# RGB_Station_v11.net
KiCad netlist of a schematic drawn in EAGLE
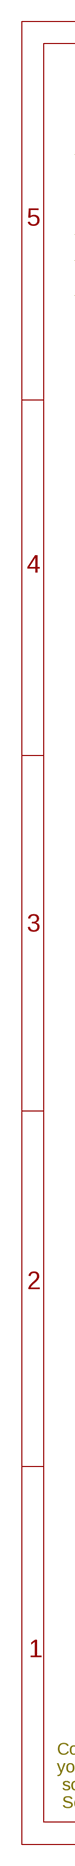
[diagram p0: schematic, sheet 1, part 1 of 2]
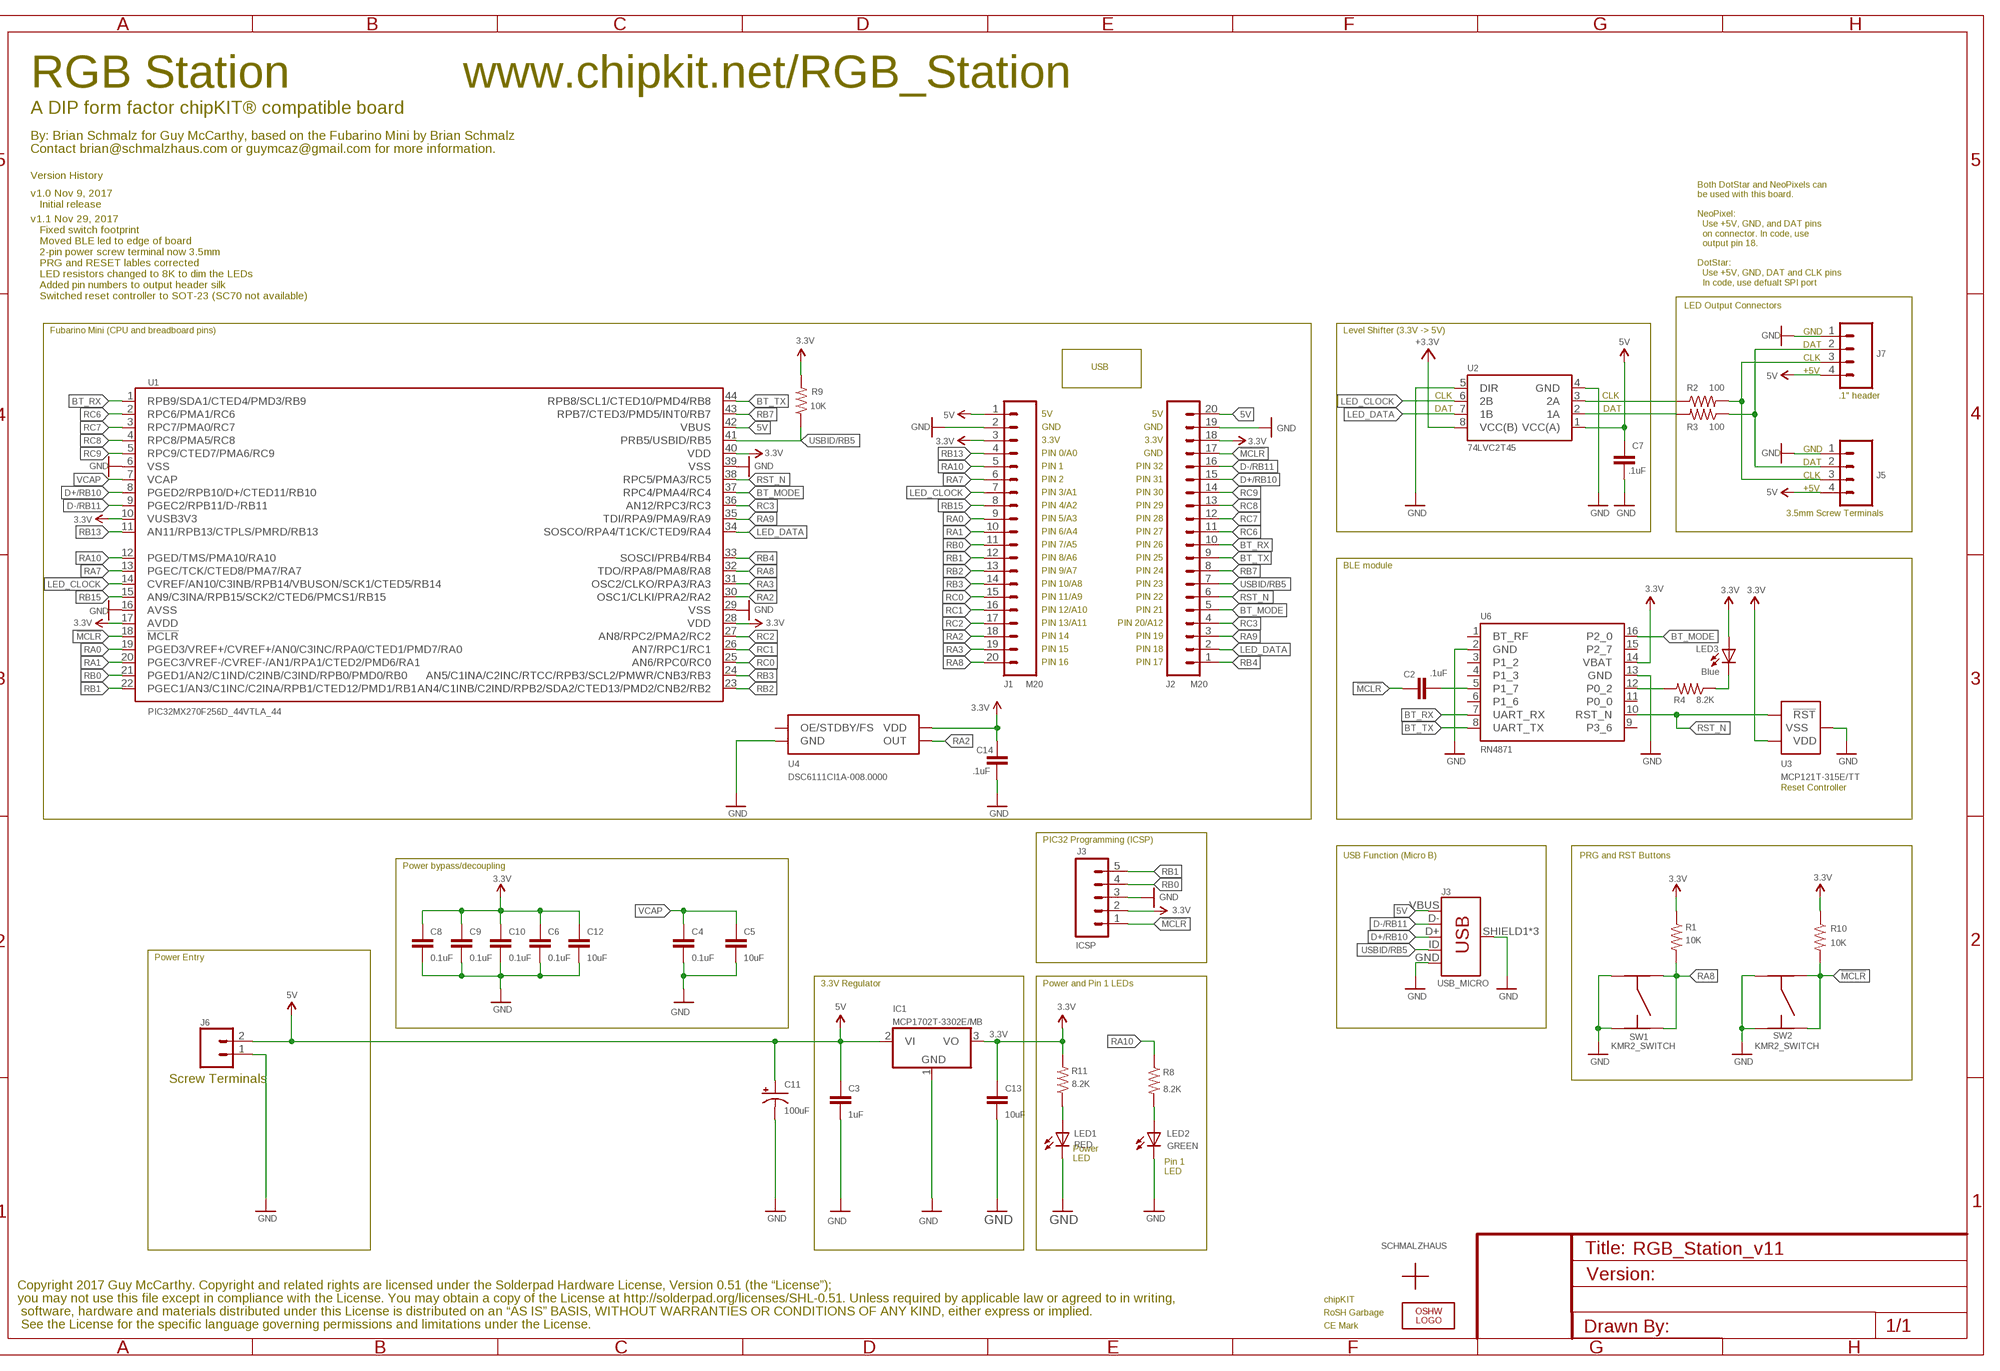
[diagram p1: schematic, sheet 1, part 2 of 2]

(export (version "E")
  (design (tool "Eeschema 10.0.6"))
  (components
    (comp (ref "C2")
      (value ".1uF")
      (footprint "eagle-import:0603-CAP")
      (libsource (lib "eagle-import") (part "SparkFun-Capacitors_CAP0603-CAP"))
    )
    (comp (ref "C3")
      (value "1uF")
      (footprint "eagle-import:0603-CAP")
      (libsource (lib "eagle-import") (part "SparkFun_CAP0603-CAP"))
    )
    (comp (ref "C4")
      (value "0.1uF")
      (footprint "eagle-import:0603-CAP")
      (libsource (lib "eagle-import") (part "SparkFun_CAP0603-CAP"))
    )
    (comp (ref "C5")
      (value "10uF")
      (footprint "eagle-import:0805")
      (libsource (lib "eagle-import") (part "CAP0805"))
    )
    (comp (ref "C6")
      (value "0.1uF")
      (footprint "eagle-import:0603")
      (libsource (lib "eagle-import") (part "CAP0603"))
    )
    (comp (ref "C7")
      (value ".1uF")
      (footprint "eagle-import:0603-CAP")
      (libsource (lib "eagle-import") (part "SparkFun-Capacitors_CAP0603-CAP"))
    )
    (comp (ref "C8")
      (value "0.1uF")
      (footprint "eagle-import:0603-CAP")
      (libsource (lib "eagle-import") (part "SparkFun_CAP0603-CAP"))
    )
    (comp (ref "C9")
      (value "0.1uF")
      (footprint "eagle-import:0603-CAP")
      (libsource (lib "eagle-import") (part "SparkFun_CAP0603-CAP"))
    )
    (comp (ref "C10")
      (value "0.1uF")
      (footprint "eagle-import:0603")
      (libsource (lib "eagle-import") (part "CAP0603"))
    )
    (comp (ref "C11")
      (value "100uF")
      (footprint "eagle-import:PANASONIC_C")
      (libsource (lib "eagle-import") (part "CAP_POLC"))
    )
    (comp (ref "C12")
      (value "10uF")
      (footprint "eagle-import:0805")
      (libsource (lib "eagle-import") (part "CAP0805"))
    )
    (comp (ref "C13")
      (value "10uF")
      (footprint "eagle-import:0805")
      (libsource (lib "eagle-import") (part "SparkFun02-20-08_CAP0805"))
    )
    (comp (ref "C14")
      (value ".1uF")
      (footprint "eagle-import:0603-CAP")
      (libsource (lib "eagle-import") (part "SparkFun_CAP0603-CAP"))
    )
    (comp (ref "IC1")
      (value "MCP1702T-3302E/MB")
      (footprint "eagle-import:SOT89")
      (libsource (lib "eagle-import") (part "MCP1703MB33"))
    )
    (comp (ref "ICSP")
      (value "J3")
      (footprint "eagle-import:1X05_NOSILK")
      (libsource (lib "eagle-import") (part "M05NOSLILK"))
    )
    (comp (ref "J1")
      (value "M20")
      (footprint "eagle-import:1X20_NO_PIN1")
      (libsource (lib "eagle-import") (part "M20"))
    )
    (comp (ref "J2")
      (value "M20")
      (footprint "eagle-import:1X20_NO_PIN1")
      (libsource (lib "eagle-import") (part "M20"))
    )
    (comp (ref "J3")
      (value "USB_MICRO")
      (footprint "eagle-import:USB-B-MICRO-SMD")
      (libsource (lib "eagle-import") (part "USB_MICRO-B_FEMALE-SMT"))
    )
    (comp (ref "J5")
      (value "CONN_04SCREW")
      (footprint "eagle-import:SCREWTERMINAL-3.5MM-4@1")
      (libsource (lib "eagle-import") (part "CONN_04SCREW"))
    )
    (comp (ref "J6")
      (value "CONN_023.5MM")
      (footprint "eagle-import:SCREWTERMINAL-3.5MM-2")
      (libsource (lib "eagle-import") (part "CONN_023.5MM"))
    )
    (comp (ref "J7")
      (value "M04PTH")
      (footprint "eagle-import:1X04")
      (libsource (lib "eagle-import") (part "M04PTH"))
    )
    (comp (ref "LED1")
      (value "RED")
      (footprint "eagle-import:LED-0603")
      (libsource (lib "eagle-import") (part "LED0603"))
    )
    (comp (ref "LED2")
      (value "GREEN")
      (footprint "eagle-import:LED-0603")
      (libsource (lib "eagle-import") (part "LED0603"))
    )
    (comp (ref "LED3")
      (value "Blue")
      (footprint "eagle-import:LED-0603")
      (libsource (lib "eagle-import") (part "LED0603"))
    )
    (comp (ref "LOGO1")
      (value "OSHW_LOGO_8MILX0070-NT")
      (footprint "eagle-import:OSHW_8X70_NOTEXT")
      (libsource (lib "eagle-import") (part "OSHW_LOGO_8MILX0070-NT"))
    )
    (comp (ref "R1")
      (value "10K")
      (footprint "eagle-import:0603-RES")
      (libsource (lib "eagle-import") (part "RESISTOR0603-RES"))
    )
    (comp (ref "R2")
      (value "100")
      (footprint "eagle-import:0603-RES")
      (libsource (lib "eagle-import") (part "RESISTOR0603"))
    )
    (comp (ref "R3")
      (value "100")
      (footprint "eagle-import:0603-RES")
      (libsource (lib "eagle-import") (part "RESISTOR0603"))
    )
    (comp (ref "R4")
      (value "8.2K")
      (footprint "eagle-import:0603-RES")
      (libsource (lib "eagle-import") (part "RESISTOR0603-RES"))
    )
    (comp (ref "R8")
      (value "8.2K")
      (footprint "eagle-import:0603-RES")
      (libsource (lib "eagle-import") (part "RESISTOR0603-RES"))
    )
    (comp (ref "R9")
      (value "10K")
      (footprint "eagle-import:0603-RES")
      (libsource (lib "eagle-import") (part "RESISTOR0603-RES"))
    )
    (comp (ref "R10")
      (value "10K")
      (footprint "eagle-import:0603-RES")
      (libsource (lib "eagle-import") (part "RESISTOR0603-RES"))
    )
    (comp (ref "R11")
      (value "8.2K")
      (footprint "eagle-import:0603-RES")
      (libsource (lib "eagle-import") (part "RESISTOR0603-RES"))
    )
    (comp (ref "SW1")
      (value "KMR2_SWITCH")
      (footprint "eagle-import:KMR2_SWITCH")
      (libsource (lib "eagle-import") (part "KMR2_SWITCH"))
    )
    (comp (ref "SW2")
      (value "KMR2_SWITCH")
      (footprint "eagle-import:KMR2_SWITCH")
      (libsource (lib "eagle-import") (part "KMR2_SWITCH"))
    )
    (comp (ref "U$2")
      (value "CE_MARK5MM")
      (footprint "eagle-import:CE_5MM")
      (libsource (lib "eagle-import") (part "CE_MARK5MM"))
    )
    (comp (ref "U$3")
      (value "ROSH_GARBAGE")
      (footprint "eagle-import:ROHS_GARBAGE_5MM")
      (libsource (lib "eagle-import") (part "ROSH_GARBAGE"))
    )
    (comp (ref "U$4")
      (value "CHIPKIT2MM")
      (footprint "eagle-import:CHIPKIT_2MM")
      (libsource (lib "eagle-import") (part "CHIPKIT2MM"))
    )
    (comp (ref "U$5")
      (value "SCHMALZHAUSSCHMALZHAUS_SMALL")
      (footprint "eagle-import:SCHMALZHAUS_SMALL")
      (libsource (lib "eagle-import") (part "SCHMALZHAUSSCHMALZHAUS_SMALL"))
    )
    (comp (ref "U1")
      (value "PIC32MX270F256D_44VTLA_44")
      (footprint "eagle-import:QFN-44-8X8-NOPAD")
      (libsource (lib "eagle-import") (part "PIC32MX2XX_44QFN44"))
    )
    (comp (ref "U2")
      (value "74LVC2T45")
      (footprint "eagle-import:VSSOP8")
      (libsource (lib "eagle-import") (part "74LVC2T45"))
    )
    (comp (ref "U3")
      (value "MCP121T-315E/TT")
      (footprint "eagle-import:SOT23-3")
      (libsource (lib "eagle-import") (part "MCP1X2_RESET_CONTROLLER"))
    )
    (comp (ref "U4")
      (value "DSC6111CI1A-008.0000")
      (footprint "eagle-import:CDFN-4_3.2X2.5")
      (libsource (lib "eagle-import") (part "DSC61XX"))
    )
    (comp (ref "U6")
      (value "RN4871")
      (footprint "eagle-import:RN4871")
      (libsource (lib "eagle-import") (part "RN4871"))
    )
  )
  (nets
    (net (code "1") (name "+3.3V") (class "Default")
      (node (ref "C10") (pin "1") (pinfunction "1_1") (pintype "passive"))
      (node (ref "C12") (pin "1") (pinfunction "1_1") (pintype "passive"))
      (node (ref "C13") (pin "1") (pinfunction "1_1") (pintype "passive"))
      (node (ref "C14") (pin "2") (pinfunction "2_2") (pintype "passive"))
      (node (ref "C6") (pin "1") (pinfunction "1_1") (pintype "passive"))
      (node (ref "C8") (pin "1") (pinfunction "1_1") (pintype "passive"))
      (node (ref "C9") (pin "1") (pinfunction "1_1") (pintype "passive"))
      (node (ref "IC1") (pin "3") (pinfunction "VO_3") (pintype "passive"))
      (node (ref "ICSP") (pin "2") (pinfunction "2_2") (pintype "passive"))
      (node (ref "J1") (pin "3") (pinfunction "3_3") (pintype "passive"))
      (node (ref "J2") (pin "18") (pinfunction "18_18") (pintype "passive"))
      (node (ref "LED3") (pin "A") (pinfunction "A_A") (pintype "passive"))
      (node (ref "R1") (pin "1") (pinfunction "1_1") (pintype "passive"))
      (node (ref "R10") (pin "1") (pinfunction "1_1") (pintype "passive"))
      (node (ref "R11") (pin "2") (pinfunction "2_2") (pintype "passive"))
      (node (ref "R9") (pin "2") (pinfunction "2_2") (pintype "passive"))
      (node (ref "U1") (pin "10") (pinfunction "VUSB3V3_10") (pintype "bidirectional"))
      (node (ref "U1") (pin "17") (pinfunction "AVDD_17") (pintype "bidirectional"))
      (node (ref "U1") (pin "28") (pinfunction "VDD_28") (pintype "bidirectional"))
      (node (ref "U1") (pin "40") (pinfunction "VDD_40") (pintype "bidirectional"))
      (node (ref "U2") (pin "8") (pinfunction "VCC(B)_8") (pintype "bidirectional"))
      (node (ref "U3") (pin "2") (pinfunction "VDD_2") (pintype "bidirectional"))
      (node (ref "U4") (pin "P4") (pinfunction "VDD_P4") (pintype "bidirectional"))
      (node (ref "U6") (pin "14") (pinfunction "VBAT_14") (pintype "bidirectional"))
    )
    (net (code "2") (name "/~{MCLR}") (class "Default")
      (node (ref "C2") (pin "2") (pinfunction "2_2") (pintype "passive"))
      (node (ref "ICSP") (pin "1") (pinfunction "1_1") (pintype "passive"))
      (node (ref "J2") (pin "17") (pinfunction "17_17") (pintype "passive"))
      (node (ref "R10") (pin "2") (pinfunction "2_2") (pintype "passive"))
      (node (ref "SW2") (pin "P3") (pinfunction "P3_P3") (pintype "bidirectional"))
      (node (ref "SW2") (pin "P4") (pinfunction "P4_P4") (pintype "bidirectional"))
      (node (ref "U1") (pin "18") (pinfunction "~{MCLR}_18") (pintype "bidirectional"))
    )
    (net (code "3") (name "5V") (class "Default")
      (node (ref "C11") (pin "+") (pinfunction "+_+") (pintype "passive"))
      (node (ref "C3") (pin "1") (pinfunction "1_1") (pintype "passive"))
      (node (ref "C7") (pin "2") (pinfunction "2_2") (pintype "passive"))
      (node (ref "IC1") (pin "2") (pinfunction "VI_2") (pintype "input"))
      (node (ref "IC1") (pin "2@1") (pinfunction "VI1_2@1") (pintype "input"))
      (node (ref "J1") (pin "1") (pinfunction "1_1") (pintype "passive"))
      (node (ref "J2") (pin "20") (pinfunction "20_20") (pintype "passive"))
      (node (ref "J3") (pin "VBUS") (pinfunction "VBUS_VBUS") (pintype "power_in"))
      (node (ref "J5") (pin "4") (pinfunction "4_4") (pintype "passive"))
      (node (ref "J6") (pin "2") (pinfunction "2_2") (pintype "passive"))
      (node (ref "J7") (pin "4") (pinfunction "4_4") (pintype "passive"))
      (node (ref "U1") (pin "42") (pinfunction "VBUS_42") (pintype "bidirectional"))
      (node (ref "U2") (pin "1") (pinfunction "VCC(A)_1") (pintype "bidirectional"))
    )
    (net (code "4") (name "BT_MODE") (class "Default")
      (node (ref "J2") (pin "5") (pinfunction "5_5") (pintype "passive"))
      (node (ref "U1") (pin "37") (pinfunction "RPC4/PMA4/RC4_37") (pintype "bidirectional"))
      (node (ref "U6") (pin "16") (pinfunction "P2_0_16") (pintype "bidirectional"))
    )
    (net (code "5") (name "BT_RX") (class "Default")
      (node (ref "J2") (pin "10") (pinfunction "10_10") (pintype "passive"))
      (node (ref "U1") (pin "1") (pinfunction "RPB9/SDA1/CTED4/PMD3/RB9_1") (pintype "bidirectional"))
      (node (ref "U6") (pin "7") (pinfunction "UART_RX_7") (pintype "bidirectional"))
    )
    (net (code "6") (name "BT_TX") (class "Default")
      (node (ref "J2") (pin "9") (pinfunction "9_9") (pintype "passive"))
      (node (ref "U1") (pin "44") (pinfunction "RPB8/SCL1/CTED10/PMD4/RB8_44") (pintype "bidirectional"))
      (node (ref "U6") (pin "8") (pinfunction "UART_TX_8") (pintype "bidirectional"))
    )
    (net (code "7") (name "D+{slash}RB10") (class "Default")
      (node (ref "J2") (pin "15") (pinfunction "15_15") (pintype "passive"))
      (node (ref "J3") (pin "D+") (pinfunction "D+_D+") (pintype "bidirectional"))
      (node (ref "U1") (pin "8") (pinfunction "PGED2/RPB10/D+/CTED11/RB10_8") (pintype "bidirectional"))
    )
    (net (code "8") (name "D-{slash}RB11") (class "Default")
      (node (ref "J2") (pin "16") (pinfunction "16_16") (pintype "passive"))
      (node (ref "J3") (pin "D-") (pinfunction "D-_D-") (pintype "bidirectional"))
      (node (ref "U1") (pin "9") (pinfunction "PGEC2/RPB11/D-/RB11_9") (pintype "bidirectional"))
    )
    (net (code "9") (name "GND") (class "Default")
      (node (ref "C10") (pin "2") (pinfunction "2_2") (pintype "passive"))
      (node (ref "C11") (pin "-") (pinfunction "-_-") (pintype "passive"))
      (node (ref "C12") (pin "2") (pinfunction "2_2") (pintype "passive"))
      (node (ref "C13") (pin "2") (pinfunction "2_2") (pintype "passive"))
      (node (ref "C14") (pin "1") (pinfunction "1_1") (pintype "passive"))
      (node (ref "C3") (pin "2") (pinfunction "2_2") (pintype "passive"))
      (node (ref "C4") (pin "2") (pinfunction "2_2") (pintype "passive"))
      (node (ref "C5") (pin "2") (pinfunction "2_2") (pintype "passive"))
      (node (ref "C6") (pin "2") (pinfunction "2_2") (pintype "passive"))
      (node (ref "C7") (pin "1") (pinfunction "1_1") (pintype "passive"))
      (node (ref "C8") (pin "2") (pinfunction "2_2") (pintype "passive"))
      (node (ref "C9") (pin "2") (pinfunction "2_2") (pintype "passive"))
      (node (ref "IC1") (pin "1") (pinfunction "GND_1") (pintype "passive"))
      (node (ref "ICSP") (pin "3") (pinfunction "3_3") (pintype "passive"))
      (node (ref "J1") (pin "2") (pinfunction "2_2") (pintype "passive"))
      (node (ref "J2") (pin "19") (pinfunction "19_19") (pintype "passive"))
      (node (ref "J3") (pin "GND") (pinfunction "GND_GND") (pintype "power_in"))
      (node (ref "J3") (pin "SHIELD1") (pinfunction "SHIELD_SHIELD1") (pintype "bidirectional"))
      (node (ref "J3") (pin "SHIELD2") (pinfunction "SHIELD_SHIELD2") (pintype "bidirectional"))
      (node (ref "J3") (pin "SHIELD3") (pinfunction "SHIELD_SHIELD3") (pintype "bidirectional"))
      (node (ref "J5") (pin "1") (pinfunction "1_1") (pintype "passive"))
      (node (ref "J6") (pin "1") (pinfunction "1_1") (pintype "passive"))
      (node (ref "J7") (pin "1") (pinfunction "1_1") (pintype "passive"))
      (node (ref "LED1") (pin "C") (pinfunction "C_C") (pintype "passive"))
      (node (ref "LED2") (pin "C") (pinfunction "C_C") (pintype "passive"))
      (node (ref "SW1") (pin "P1") (pinfunction "P1_P1") (pintype "bidirectional"))
      (node (ref "SW1") (pin "P2") (pinfunction "P2_P2") (pintype "bidirectional"))
      (node (ref "SW2") (pin "P1") (pinfunction "P1_P1") (pintype "bidirectional"))
      (node (ref "SW2") (pin "P2") (pinfunction "P2_P2") (pintype "bidirectional"))
      (node (ref "U1") (pin "16") (pinfunction "AVSS_16") (pintype "bidirectional"))
      (node (ref "U1") (pin "29") (pinfunction "VSS_29") (pintype "bidirectional"))
      (node (ref "U1") (pin "39") (pinfunction "VSS_39") (pintype "bidirectional"))
      (node (ref "U1") (pin "6") (pinfunction "VSS_6") (pintype "bidirectional"))
      (node (ref "U2") (pin "4") (pinfunction "GND_4") (pintype "bidirectional"))
      (node (ref "U2") (pin "5") (pinfunction "DIR_5") (pintype "bidirectional"))
      (node (ref "U3") (pin "3") (pinfunction "VSS_3") (pintype "bidirectional"))
      (node (ref "U4") (pin "P2") (pinfunction "GND_P2") (pintype "bidirectional"))
      (node (ref "U6") (pin "13") (pinfunction "GND_13") (pintype "bidirectional"))
      (node (ref "U6") (pin "2") (pinfunction "GND_2") (pintype "bidirectional"))
    )
    (net (code "10") (name "LED_CLOCK") (class "Default")
      (node (ref "J1") (pin "7") (pinfunction "7_7") (pintype "passive"))
      (node (ref "U1") (pin "14") (pinfunction "CVREF/AN10/C3INB/RPB14/VBUSON/SCK1/CTED5/RB14_14") (pintype "bidirectional"))
      (node (ref "U2") (pin "6") (pinfunction "2B_6") (pintype "bidirectional"))
    )
    (net (code "11") (name "LED_DATA") (class "Default")
      (node (ref "J2") (pin "2") (pinfunction "2_2") (pintype "passive"))
      (node (ref "U1") (pin "34") (pinfunction "SOSCO/RPA4/T1CK/CTED9/RA4_34") (pintype "bidirectional"))
      (node (ref "U2") (pin "7") (pinfunction "1B_7") (pintype "bidirectional"))
    )
    (net (code "12") (name "Net-(J5-Pad2)") (class "Default")
      (node (ref "J5") (pin "2") (pinfunction "2_2") (pintype "passive"))
      (node (ref "J7") (pin "2") (pinfunction "2_2") (pintype "passive"))
      (node (ref "R3") (pin "1") (pinfunction "1_1") (pintype "passive"))
    )
    (net (code "13") (name "Net-(J5-Pad3)") (class "Default")
      (node (ref "J5") (pin "3") (pinfunction "3_3") (pintype "passive"))
      (node (ref "J7") (pin "3") (pinfunction "3_3") (pintype "passive"))
      (node (ref "R2") (pin "2") (pinfunction "2_2") (pintype "passive"))
    )
    (net (code "14") (name "Net-(LED1-PadA)") (class "Default")
      (node (ref "LED1") (pin "A") (pinfunction "A_A") (pintype "passive"))
      (node (ref "R11") (pin "1") (pinfunction "1_1") (pintype "passive"))
    )
    (net (code "15") (name "Net-(LED2-PadA)") (class "Default")
      (node (ref "LED2") (pin "A") (pinfunction "A_A") (pintype "passive"))
      (node (ref "R8") (pin "2") (pinfunction "2_2") (pintype "passive"))
    )
    (net (code "16") (name "Net-(LED3-PadC)") (class "Default")
      (node (ref "LED3") (pin "C") (pinfunction "C_C") (pintype "passive"))
      (node (ref "R4") (pin "1") (pinfunction "1_1") (pintype "passive"))
    )
    (net (code "17") (name "Net-(U2-1A)") (class "Default")
      (node (ref "R3") (pin "2") (pinfunction "2_2") (pintype "passive"))
      (node (ref "U2") (pin "2") (pinfunction "1A_2") (pintype "bidirectional"))
    )
    (net (code "18") (name "Net-(U2-2A)") (class "Default")
      (node (ref "R2") (pin "1") (pinfunction "1_1") (pintype "passive"))
      (node (ref "U2") (pin "3") (pinfunction "2A_3") (pintype "bidirectional"))
    )
    (net (code "19") (name "Net-(U6-P0_2)") (class "Default")
      (node (ref "R4") (pin "2") (pinfunction "2_2") (pintype "passive"))
      (node (ref "U6") (pin "12") (pinfunction "P0_2_12") (pintype "bidirectional"))
    )
    (net (code "20") (name "Net-(U6-P1_7)") (class "Default")
      (node (ref "C2") (pin "1") (pinfunction "1_1") (pintype "passive"))
      (node (ref "U6") (pin "5") (pinfunction "P1_7_5") (pintype "bidirectional"))
    )
    (net (code "21") (name "RA0") (class "Default")
      (node (ref "J1") (pin "9") (pinfunction "9_9") (pintype "passive"))
      (node (ref "U1") (pin "19") (pinfunction "PGED3/VREF+/CVREF+/AN0/C3INC/RPA0/CTED1/PMD7/RA0_19") (pintype "bidirectional"))
    )
    (net (code "22") (name "RA1") (class "Default")
      (node (ref "J1") (pin "10") (pinfunction "10_10") (pintype "passive"))
      (node (ref "U1") (pin "20") (pinfunction "PGEC3/VREF-/CVREF-/AN1/RPA1/CTED2/PMD6/RA1_20") (pintype "bidirectional"))
    )
    (net (code "23") (name "RA2") (class "Default")
      (node (ref "J1") (pin "18") (pinfunction "18_18") (pintype "passive"))
      (node (ref "U1") (pin "30") (pinfunction "OSC1/CLKI/PRA2/RA2_30") (pintype "bidirectional"))
      (node (ref "U4") (pin "P3") (pinfunction "OUT_P3") (pintype "bidirectional"))
    )
    (net (code "24") (name "RA3") (class "Default")
      (node (ref "J1") (pin "19") (pinfunction "19_19") (pintype "passive"))
      (node (ref "U1") (pin "31") (pinfunction "OSC2/CLKO/RPA3/RA3_31") (pintype "bidirectional"))
    )
    (net (code "25") (name "RA7") (class "Default")
      (node (ref "J1") (pin "6") (pinfunction "6_6") (pintype "passive"))
      (node (ref "U1") (pin "13") (pinfunction "PGEC/TCK/CTED8/PMA7/RA7_13") (pintype "bidirectional"))
    )
    (net (code "26") (name "RA8") (class "Default")
      (node (ref "J1") (pin "20") (pinfunction "20_20") (pintype "passive"))
      (node (ref "R1") (pin "2") (pinfunction "2_2") (pintype "passive"))
      (node (ref "SW1") (pin "P3") (pinfunction "P3_P3") (pintype "bidirectional"))
      (node (ref "SW1") (pin "P4") (pinfunction "P4_P4") (pintype "bidirectional"))
      (node (ref "U1") (pin "32") (pinfunction "TDO/RPA8/PMA8/RA8_32") (pintype "bidirectional"))
    )
    (net (code "27") (name "RA9") (class "Default")
      (node (ref "J2") (pin "3") (pinfunction "3_3") (pintype "passive"))
      (node (ref "U1") (pin "35") (pinfunction "TDI/RPA9/PMA9/RA9_35") (pintype "bidirectional"))
    )
    (net (code "28") (name "RA10") (class "Default")
      (node (ref "J1") (pin "5") (pinfunction "5_5") (pintype "passive"))
      (node (ref "R8") (pin "1") (pinfunction "1_1") (pintype "passive"))
      (node (ref "U1") (pin "12") (pinfunction "PGED/TMS/PMA10/RA10_12") (pintype "bidirectional"))
    )
    (net (code "29") (name "RB0") (class "Default")
      (node (ref "ICSP") (pin "4") (pinfunction "4_4") (pintype "passive"))
      (node (ref "J1") (pin "11") (pinfunction "11_11") (pintype "passive"))
      (node (ref "U1") (pin "21") (pinfunction "PGED1/AN2/C1IND/C2INB/C3IND/RPB0/PMD0/RB0_21") (pintype "bidirectional"))
    )
    (net (code "30") (name "RB1") (class "Default")
      (node (ref "ICSP") (pin "5") (pinfunction "5_5") (pintype "passive"))
      (node (ref "J1") (pin "12") (pinfunction "12_12") (pintype "passive"))
      (node (ref "U1") (pin "22") (pinfunction "PGEC1/AN3/C1INC/C2INA/RPB1/CTED12/PMD1/RB1_22") (pintype "bidirectional"))
    )
    (net (code "31") (name "RB2") (class "Default")
      (node (ref "J1") (pin "13") (pinfunction "13_13") (pintype "passive"))
      (node (ref "U1") (pin "23") (pinfunction "AN4/C1INB/C2IND/RPB2/SDA2/CTED13/PMD2/CNB2/RB2_23") (pintype "bidirectional"))
    )
    (net (code "32") (name "RB3") (class "Default")
      (node (ref "J1") (pin "14") (pinfunction "14_14") (pintype "passive"))
      (node (ref "U1") (pin "24") (pinfunction "AN5/C1INA/C2INC/RTCC/RPB3/SCL2/PMWR/CNB3/RB3_24") (pintype "bidirectional"))
    )
    (net (code "33") (name "RB4") (class "Default")
      (node (ref "J2") (pin "1") (pinfunction "1_1") (pintype "passive"))
      (node (ref "U1") (pin "33") (pinfunction "SOSCI/PRB4/RB4_33") (pintype "bidirectional"))
    )
    (net (code "34") (name "RB7") (class "Default")
      (node (ref "J2") (pin "8") (pinfunction "8_8") (pintype "passive"))
      (node (ref "U1") (pin "43") (pinfunction "RPB7/CTED3/PMD5/INT0/RB7_43") (pintype "bidirectional"))
    )
    (net (code "35") (name "RB13") (class "Default")
      (node (ref "J1") (pin "4") (pinfunction "4_4") (pintype "passive"))
      (node (ref "U1") (pin "11") (pinfunction "AN11/RPB13/CTPLS/PMRD/RB13_11") (pintype "bidirectional"))
    )
    (net (code "36") (name "RB15") (class "Default")
      (node (ref "J1") (pin "8") (pinfunction "8_8") (pintype "passive"))
      (node (ref "U1") (pin "15") (pinfunction "AN9/C3INA/RPB15/SCK2/CTED6/PMCS1/RB15_15") (pintype "bidirectional"))
    )
    (net (code "37") (name "RC0") (class "Default")
      (node (ref "J1") (pin "15") (pinfunction "15_15") (pintype "passive"))
      (node (ref "U1") (pin "25") (pinfunction "AN6/RPC0/RC0_25") (pintype "bidirectional"))
    )
    (net (code "38") (name "RC1") (class "Default")
      (node (ref "J1") (pin "16") (pinfunction "16_16") (pintype "passive"))
      (node (ref "U1") (pin "26") (pinfunction "AN7/RPC1/RC1_26") (pintype "bidirectional"))
    )
    (net (code "39") (name "RC2") (class "Default")
      (node (ref "J1") (pin "17") (pinfunction "17_17") (pintype "passive"))
      (node (ref "U1") (pin "27") (pinfunction "AN8/RPC2/PMA2/RC2_27") (pintype "bidirectional"))
    )
    (net (code "40") (name "RC3") (class "Default")
      (node (ref "J2") (pin "4") (pinfunction "4_4") (pintype "passive"))
      (node (ref "U1") (pin "36") (pinfunction "AN12/RPC3/RC3_36") (pintype "bidirectional"))
    )
    (net (code "41") (name "RC6") (class "Default")
      (node (ref "J2") (pin "11") (pinfunction "11_11") (pintype "passive"))
      (node (ref "U1") (pin "2") (pinfunction "RPC6/PMA1/RC6_2") (pintype "bidirectional"))
    )
    (net (code "42") (name "RC7") (class "Default")
      (node (ref "J2") (pin "12") (pinfunction "12_12") (pintype "passive"))
      (node (ref "U1") (pin "3") (pinfunction "RPC7/PMA0/RC7_3") (pintype "bidirectional"))
    )
    (net (code "43") (name "RC8") (class "Default")
      (node (ref "J2") (pin "13") (pinfunction "13_13") (pintype "passive"))
      (node (ref "U1") (pin "4") (pinfunction "RPC8/PMA5/RC8_4") (pintype "bidirectional"))
    )
    (net (code "44") (name "RC9") (class "Default")
      (node (ref "J2") (pin "14") (pinfunction "14_14") (pintype "passive"))
      (node (ref "U1") (pin "5") (pinfunction "RPC9/CTED7/PMA6/RC9_5") (pintype "bidirectional"))
    )
    (net (code "45") (name "RST_N") (class "Default")
      (node (ref "J2") (pin "6") (pinfunction "6_6") (pintype "passive"))
      (node (ref "U1") (pin "38") (pinfunction "RPC5/PMA3/RC5_38") (pintype "bidirectional"))
      (node (ref "U3") (pin "1") (pinfunction "~{RST}_1") (pintype "bidirectional"))
      (node (ref "U6") (pin "10") (pinfunction "RST_N_10") (pintype "bidirectional"))
    )
    (net (code "46") (name "USBID{slash}RB5") (class "Default")
      (node (ref "J2") (pin "7") (pinfunction "7_7") (pintype "passive"))
      (node (ref "J3") (pin "ID") (pinfunction "ID_ID") (pintype "bidirectional"))
      (node (ref "R9") (pin "1") (pinfunction "1_1") (pintype "passive"))
      (node (ref "U1") (pin "41") (pinfunction "PRB5/USBID/RB5_41") (pintype "bidirectional"))
    )
    (net (code "47") (name "VCAP") (class "Default")
      (node (ref "C4") (pin "1") (pinfunction "1_1") (pintype "passive"))
      (node (ref "C5") (pin "1") (pinfunction "1_1") (pintype "passive"))
      (node (ref "U1") (pin "7") (pinfunction "VCAP_7") (pintype "bidirectional"))
    )
    (net (code "48") (name "unconnected-(U4-OE{slash}STDBY{slash}FS-PadP1)") (class "Default")
      (node (ref "U4") (pin "P1") (pinfunction "OE/STDBY/FS_P1") (pintype "bidirectional"))
    )
    (net (code "49") (name "unconnected-(U6-BT_RF-Pad1)") (class "Default")
      (node (ref "U6") (pin "1") (pinfunction "BT_RF_1") (pintype "bidirectional"))
    )
    (net (code "50") (name "unconnected-(U6-P0_0-Pad11)") (class "Default")
      (node (ref "U6") (pin "11") (pinfunction "P0_0_11") (pintype "bidirectional"))
    )
    (net (code "51") (name "unconnected-(U6-P1_2-Pad3)") (class "Default")
      (node (ref "U6") (pin "3") (pinfunction "P1_2_3") (pintype "bidirectional"))
    )
    (net (code "52") (name "unconnected-(U6-P1_3-Pad4)") (class "Default")
      (node (ref "U6") (pin "4") (pinfunction "P1_3_4") (pintype "bidirectional"))
    )
    (net (code "53") (name "unconnected-(U6-P1_6-Pad6)") (class "Default")
      (node (ref "U6") (pin "6") (pinfunction "P1_6_6") (pintype "bidirectional"))
    )
    (net (code "54") (name "unconnected-(U6-P2_7-Pad15)") (class "Default")
      (node (ref "U6") (pin "15") (pinfunction "P2_7_15") (pintype "bidirectional"))
    )
    (net (code "55") (name "unconnected-(U6-P3_6-Pad9)") (class "Default")
      (node (ref "U6") (pin "9") (pinfunction "P3_6_9") (pintype "bidirectional"))
    )
  )
)
